# design.net
KiCad netlist of a schematic drawn in Altium Designer
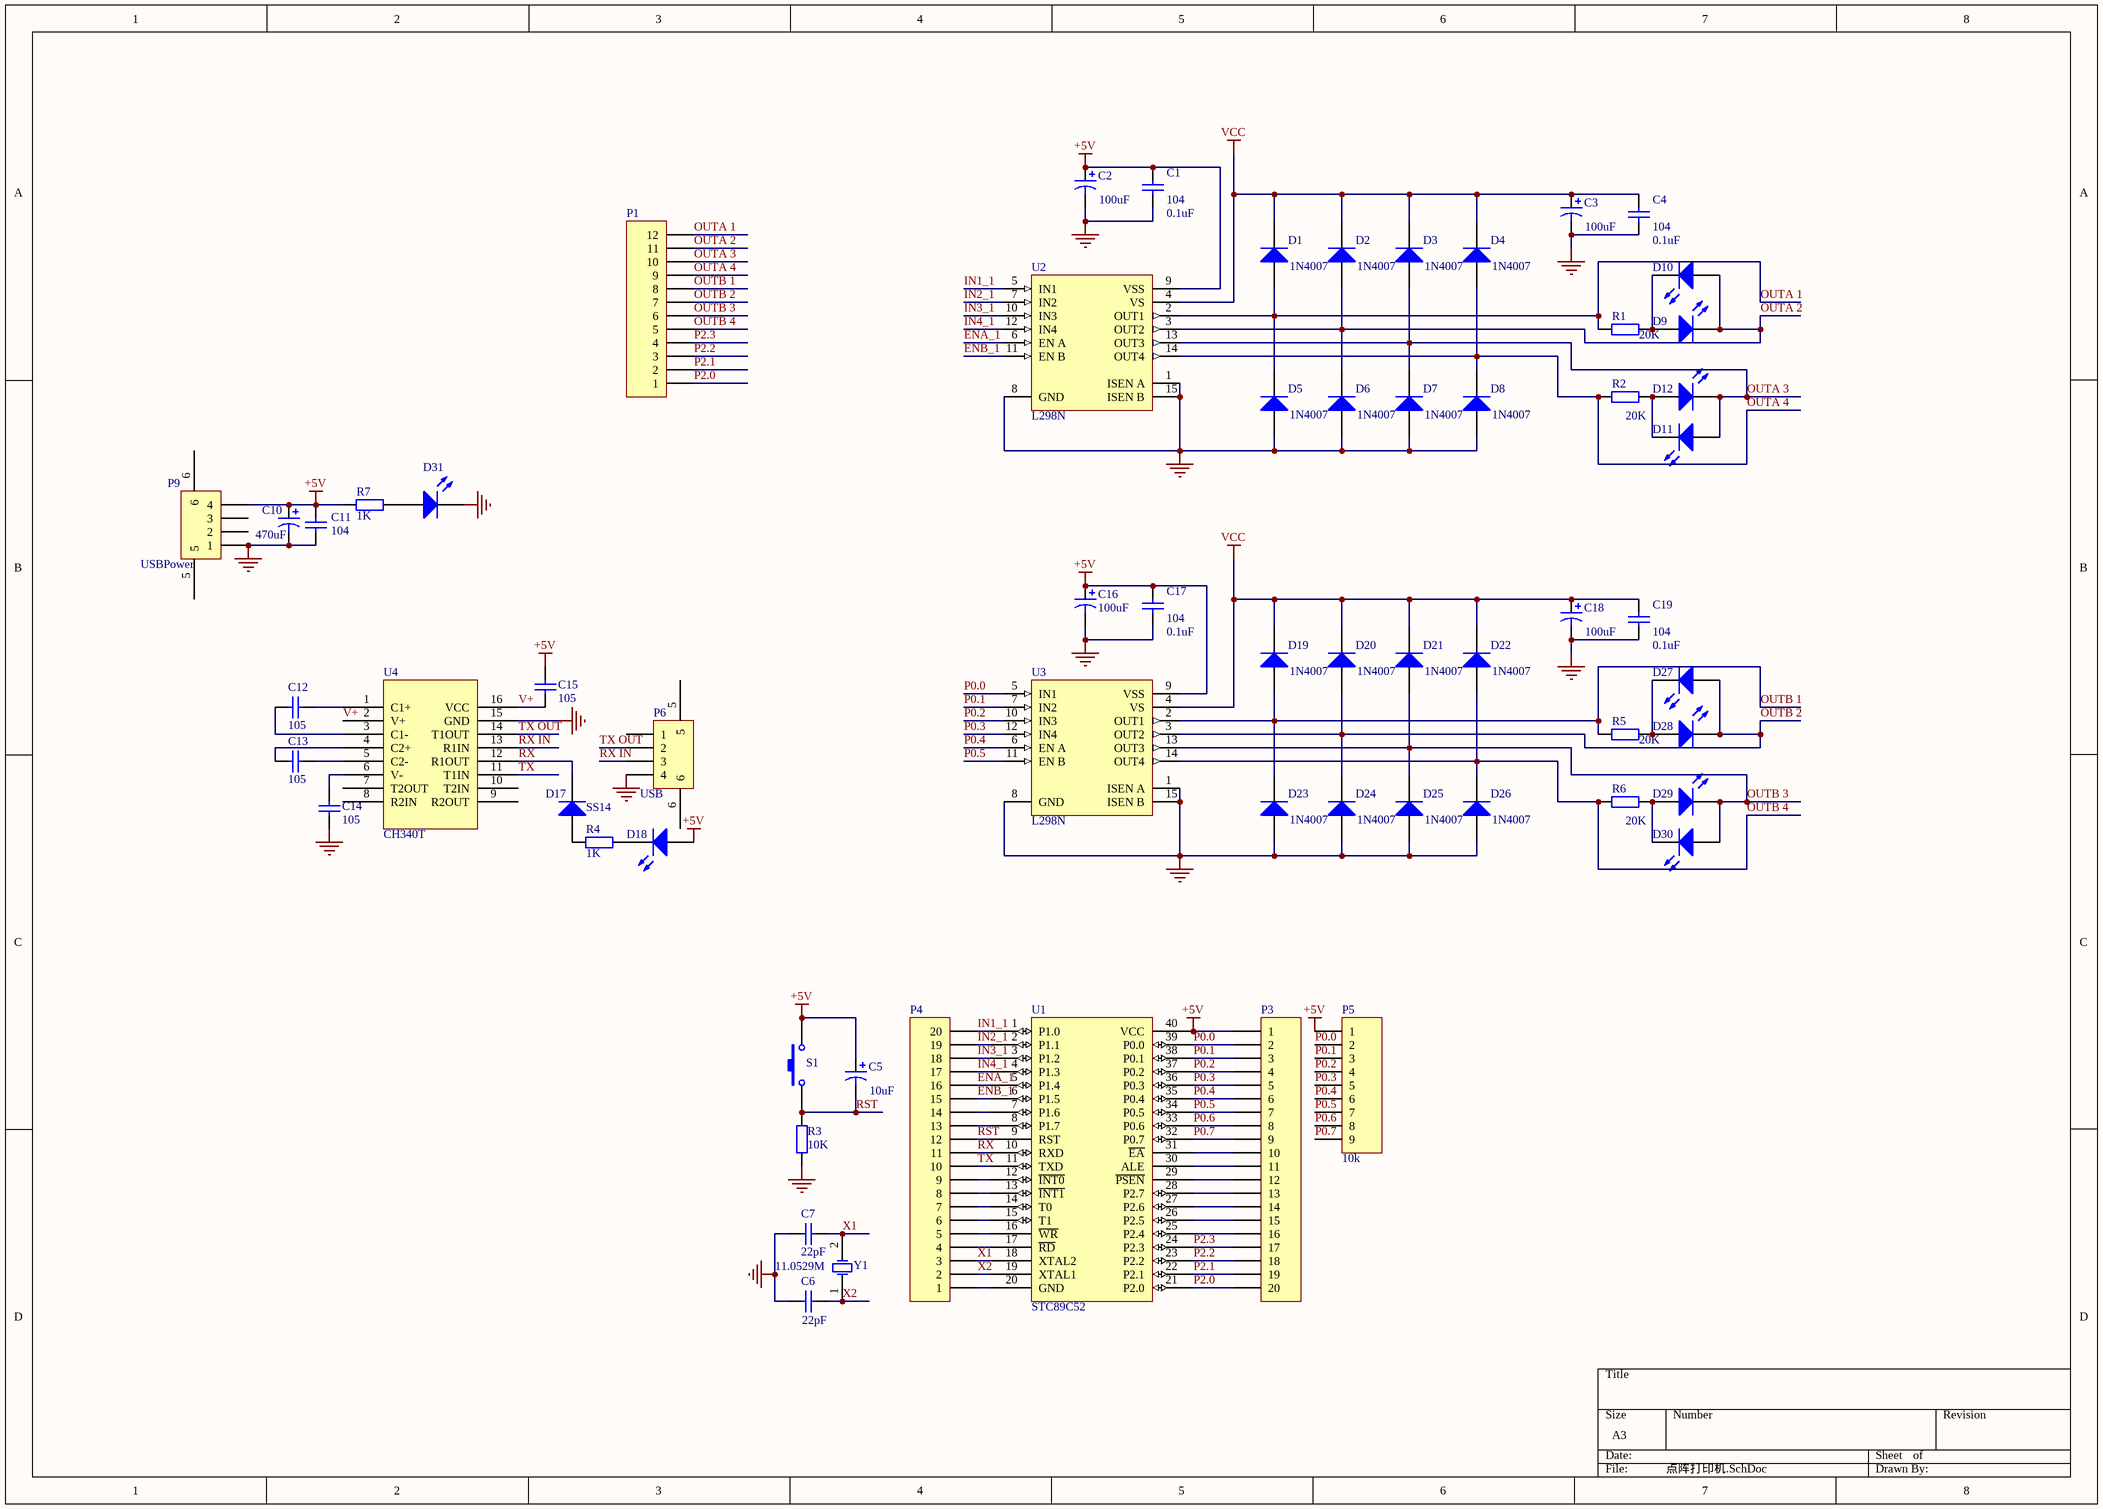
[diagram p0: 点阵打印机.SchDoc]

(export (version "E")
  (design (tool "Eeschema 10.0.6"))
  (components
    (comp (ref "C1")
      (value "0.1uF")
      (footprint "CB2")
      (description "Capacitor")
      (fields
        (field (name "ALTIUM_UNNAMED_1") "104")
        (field (name "Comment") "Cap")
        (field (name "PUBLISHER") "Altium Limited")
      )
      (libsource (lib "Miscellaneous Devices") (part "Cap"))
    )
    (comp (ref "C2")
      (value "100uF")
      (footprint "CD10")
      (description "Polarized Capacitor (Radial)")
      (fields (field (name "Comment") "Cap Pol1") (field (name "PUBLISHER") "Altium Limited"))
      (libsource (lib "Miscellaneous Devices") (part "Cap Pol1"))
    )
    (comp (ref "C3")
      (value "100uF")
      (footprint "CD10")
      (description "Polarized Capacitor (Radial)")
      (fields (field (name "Comment") "Cap Pol1") (field (name "PUBLISHER") "Altium Limited"))
      (libsource (lib "Miscellaneous Devices") (part "Cap Pol1"))
    )
    (comp (ref "C4")
      (value "0.1uF")
      (footprint "CB2")
      (description "Capacitor")
      (fields
        (field (name "ALTIUM_UNNAMED_1") "104")
        (field (name "Comment") "Cap")
        (field (name "PUBLISHER") "Altium Limited")
      )
      (libsource (lib "Miscellaneous Devices") (part "Cap"))
    )
    (comp (ref "C5")
      (value "10uF")
      (footprint "CD10")
      (description "Polarized Capacitor (Radial)")
      (fields (field (name "Comment") "Cap Pol1") (field (name "PUBLISHER") "Altium Limited"))
      (libsource (lib "Miscellaneous Devices") (part "Cap Pol1"))
    )
    (comp (ref "C6")
      (value "22pF")
      (footprint "CB2")
      (description "Capacitor")
      (fields (field (name "Comment") "Cap") (field (name "PUBLISHER") "Altium Limited"))
      (libsource (lib "Miscellaneous Devices") (part "Cap"))
    )
    (comp (ref "C7")
      (value "22pF")
      (footprint "CB2")
      (description "Capacitor")
      (fields (field (name "Comment") "Cap") (field (name "PUBLISHER") "Altium Limited"))
      (libsource (lib "Miscellaneous Devices") (part "Cap"))
    )
    (comp (ref "C10")
      (value "470uF")
      (footprint "CD10")
      (description "Polarized Capacitor (Radial)")
      (fields (field (name "Comment") "Cap Pol1") (field (name "PUBLISHER") "Altium Limited"))
      (libsource (lib "Miscellaneous Devices") (part "Cap Pol1"))
    )
    (comp (ref "C11")
      (value "104")
      (footprint "CB2")
      (description "Capacitor")
      (fields (field (name "Comment") "Cap") (field (name "PUBLISHER") "Altium Limited"))
      (libsource (lib "Miscellaneous Devices") (part "Cap"))
    )
    (comp (ref "C12")
      (value "105")
      (footprint "CB2")
      (description "Capacitor")
      (fields (field (name "Comment") "Cap") (field (name "PUBLISHER") "Altium Limited"))
      (libsource (lib "Miscellaneous Devices") (part "Cap"))
    )
    (comp (ref "C13")
      (value "105")
      (footprint "CB2")
      (description "Capacitor")
      (fields (field (name "Comment") "Cap") (field (name "PUBLISHER") "Altium Limited"))
      (libsource (lib "Miscellaneous Devices") (part "Cap"))
    )
    (comp (ref "C14")
      (value "105")
      (footprint "CB2")
      (description "Capacitor")
      (fields (field (name "Comment") "Cap") (field (name "PUBLISHER") "Altium Limited"))
      (libsource (lib "Miscellaneous Devices") (part "Cap"))
    )
    (comp (ref "C15")
      (value "105")
      (footprint "CB2")
      (description "Capacitor")
      (fields (field (name "Comment") "Cap") (field (name "PUBLISHER") "Altium Limited"))
      (libsource (lib "Miscellaneous Devices") (part "Cap"))
    )
    (comp (ref "C16")
      (value "100uF")
      (footprint "CD10")
      (description "Polarized Capacitor (Radial)")
      (fields (field (name "Comment") "Cap Pol1") (field (name "PUBLISHER") "Altium Limited"))
      (libsource (lib "Miscellaneous Devices") (part "Cap Pol1"))
    )
    (comp (ref "C17")
      (value "0.1uF")
      (footprint "CB2")
      (description "Capacitor")
      (fields
        (field (name "ALTIUM_UNNAMED_1") "104")
        (field (name "Comment") "Cap")
        (field (name "PUBLISHER") "Altium Limited")
      )
      (libsource (lib "Miscellaneous Devices") (part "Cap"))
    )
    (comp (ref "C18")
      (value "100uF")
      (footprint "CD10")
      (description "Polarized Capacitor (Radial)")
      (fields (field (name "Comment") "Cap Pol1") (field (name "PUBLISHER") "Altium Limited"))
      (libsource (lib "Miscellaneous Devices") (part "Cap Pol1"))
    )
    (comp (ref "C19")
      (value "0.1uF")
      (footprint "CB2")
      (description "Capacitor")
      (fields
        (field (name "ALTIUM_UNNAMED_1") "104")
        (field (name "Comment") "Cap")
        (field (name "PUBLISHER") "Altium Limited")
      )
      (libsource (lib "Miscellaneous Devices") (part "Cap"))
    )
    (comp (ref "D1")
      (value "1N4007")
      (footprint "DO-41")
      (description "1 Amp General Purpose Rectifier")
      (fields (field (name "PUBLISHER") "Altium Limited"))
      (libsource (lib "Miscellaneous Devices") (part "Diode 1N4007"))
    )
    (comp (ref "D2")
      (value "1N4007")
      (footprint "DO-41")
      (description "1 Amp General Purpose Rectifier")
      (fields (field (name "PUBLISHER") "Altium Limited"))
      (libsource (lib "Miscellaneous Devices") (part "Diode 1N4007"))
    )
    (comp (ref "D3")
      (value "1N4007")
      (footprint "DO-41")
      (description "1 Amp General Purpose Rectifier")
      (fields (field (name "PUBLISHER") "Altium Limited"))
      (libsource (lib "Miscellaneous Devices") (part "Diode 1N4007"))
    )
    (comp (ref "D4")
      (value "1N4007")
      (footprint "DO-41")
      (description "1 Amp General Purpose Rectifier")
      (fields (field (name "PUBLISHER") "Altium Limited"))
      (libsource (lib "Miscellaneous Devices") (part "Diode 1N4007"))
    )
    (comp (ref "D5")
      (value "1N4007")
      (footprint "DO-41")
      (description "1 Amp General Purpose Rectifier")
      (fields (field (name "PUBLISHER") "Altium Limited"))
      (libsource (lib "Miscellaneous Devices") (part "Diode 1N4007"))
    )
    (comp (ref "D6")
      (value "1N4007")
      (footprint "DO-41")
      (description "1 Amp General Purpose Rectifier")
      (fields (field (name "PUBLISHER") "Altium Limited"))
      (libsource (lib "Miscellaneous Devices") (part "Diode 1N4007"))
    )
    (comp (ref "D7")
      (value "1N4007")
      (footprint "DO-41")
      (description "1 Amp General Purpose Rectifier")
      (fields (field (name "PUBLISHER") "Altium Limited"))
      (libsource (lib "Miscellaneous Devices") (part "Diode 1N4007"))
    )
    (comp (ref "D8")
      (value "1N4007")
      (footprint "DO-41")
      (description "1 Amp General Purpose Rectifier")
      (fields (field (name "PUBLISHER") "Altium Limited"))
      (libsource (lib "Miscellaneous Devices") (part "Diode 1N4007"))
    )
    (comp (ref "D9")
      (value "LED0")
      (footprint "LED")
      (description "Typical INFRARED GaAs LED")
      (fields (field (name "PUBLISHER") "Altium Limited"))
      (libsource (lib "Miscellaneous Devices") (part "LED0"))
    )
    (comp (ref "D10")
      (value "LED0")
      (footprint "LED")
      (description "Typical INFRARED GaAs LED")
      (fields (field (name "PUBLISHER") "Altium Limited"))
      (libsource (lib "Miscellaneous Devices") (part "LED0"))
    )
    (comp (ref "D11")
      (value "LED0")
      (footprint "LED")
      (description "Typical INFRARED GaAs LED")
      (fields (field (name "PUBLISHER") "Altium Limited"))
      (libsource (lib "Miscellaneous Devices") (part "LED0"))
    )
    (comp (ref "D12")
      (value "LED0")
      (footprint "LED")
      (description "Typical INFRARED GaAs LED")
      (fields (field (name "PUBLISHER") "Altium Limited"))
      (libsource (lib "Miscellaneous Devices") (part "LED0"))
    )
    (comp (ref "D17")
      (value "SS14")
      (footprint "SMC")
      (description "Default Diode")
      (fields (field (name "PUBLISHER") "Altium Limited"))
      (libsource (lib "Miscellaneous Devices") (part "Diode"))
    )
    (comp (ref "D18")
      (value "LED0")
      (footprint "LED")
      (description "Typical INFRARED GaAs LED")
      (fields (field (name "PUBLISHER") "Altium Limited"))
      (libsource (lib "Miscellaneous Devices") (part "LED0"))
    )
    (comp (ref "D19")
      (value "1N4007")
      (footprint "DO-41")
      (description "1 Amp General Purpose Rectifier")
      (fields (field (name "PUBLISHER") "Altium Limited"))
      (libsource (lib "Miscellaneous Devices") (part "Diode 1N4007"))
    )
    (comp (ref "D20")
      (value "1N4007")
      (footprint "DO-41")
      (description "1 Amp General Purpose Rectifier")
      (fields (field (name "PUBLISHER") "Altium Limited"))
      (libsource (lib "Miscellaneous Devices") (part "Diode 1N4007"))
    )
    (comp (ref "D21")
      (value "1N4007")
      (footprint "DO-41")
      (description "1 Amp General Purpose Rectifier")
      (fields (field (name "PUBLISHER") "Altium Limited"))
      (libsource (lib "Miscellaneous Devices") (part "Diode 1N4007"))
    )
    (comp (ref "D22")
      (value "1N4007")
      (footprint "DO-41")
      (description "1 Amp General Purpose Rectifier")
      (fields (field (name "PUBLISHER") "Altium Limited"))
      (libsource (lib "Miscellaneous Devices") (part "Diode 1N4007"))
    )
    (comp (ref "D23")
      (value "1N4007")
      (footprint "DO-41")
      (description "1 Amp General Purpose Rectifier")
      (fields (field (name "PUBLISHER") "Altium Limited"))
      (libsource (lib "Miscellaneous Devices") (part "Diode 1N4007"))
    )
    (comp (ref "D24")
      (value "1N4007")
      (footprint "DO-41")
      (description "1 Amp General Purpose Rectifier")
      (fields (field (name "PUBLISHER") "Altium Limited"))
      (libsource (lib "Miscellaneous Devices") (part "Diode 1N4007"))
    )
    (comp (ref "D25")
      (value "1N4007")
      (footprint "DO-41")
      (description "1 Amp General Purpose Rectifier")
      (fields (field (name "PUBLISHER") "Altium Limited"))
      (libsource (lib "Miscellaneous Devices") (part "Diode 1N4007"))
    )
    (comp (ref "D26")
      (value "1N4007")
      (footprint "DO-41")
      (description "1 Amp General Purpose Rectifier")
      (fields (field (name "PUBLISHER") "Altium Limited"))
      (libsource (lib "Miscellaneous Devices") (part "Diode 1N4007"))
    )
    (comp (ref "D27")
      (value "LED0")
      (footprint "LED")
      (description "Typical INFRARED GaAs LED")
      (fields (field (name "PUBLISHER") "Altium Limited"))
      (libsource (lib "Miscellaneous Devices") (part "LED0"))
    )
    (comp (ref "D28")
      (value "LED0")
      (footprint "LED")
      (description "Typical INFRARED GaAs LED")
      (fields (field (name "PUBLISHER") "Altium Limited"))
      (libsource (lib "Miscellaneous Devices") (part "LED0"))
    )
    (comp (ref "D29")
      (value "LED0")
      (footprint "LED")
      (description "Typical INFRARED GaAs LED")
      (fields (field (name "PUBLISHER") "Altium Limited"))
      (libsource (lib "Miscellaneous Devices") (part "LED0"))
    )
    (comp (ref "D30")
      (value "LED0")
      (footprint "LED")
      (description "Typical INFRARED GaAs LED")
      (fields (field (name "PUBLISHER") "Altium Limited"))
      (libsource (lib "Miscellaneous Devices") (part "LED0"))
    )
    (comp (ref "D31")
      (value "LED0")
      (footprint "LED")
      (description "Typical INFRARED GaAs LED")
      (fields (field (name "PUBLISHER") "Altium Limited"))
      (libsource (lib "Miscellaneous Devices") (part "LED0"))
    )
    (comp (ref "P1")
      (value "Header 12")
      (footprint "HDR1X12")
      (description "Header, 12-Pin")
      (fields (field (name "PUBLISHER") "Altium Limited"))
      (libsource (lib "Miscellaneous Connectors") (part "Header 12"))
    )
    (comp (ref "P3")
      (value "Header 20")
      (footprint "HDR1X20")
      (description "Header, 20-Pin")
      (fields (field (name "PUBLISHER") "Altium Limited"))
      (libsource (lib "Miscellaneous Connectors") (part "Header 20"))
    )
    (comp (ref "P4")
      (value "Header 20")
      (footprint "HDR1X20")
      (description "Header, 20-Pin")
      (fields (field (name "PUBLISHER") "Altium Limited"))
      (libsource (lib "") (part "Header 20_1"))
    )
    (comp (ref "P5")
      (value "10k")
      (footprint "HDR1X9")
      (description "Header, 9-Pin")
      (fields (field (name "PUBLISHER") "Altium Limited"))
      (libsource (lib "Miscellaneous Connectors") (part "Header 9"))
    )
    (comp (ref "P6")
      (value "USB")
      (footprint "USB")
      (description "Header, 4-Pin")
      (fields (field (name "PUBLISHER") "Altium Limited"))
      (libsource (lib "") (part "Header 4_1"))
    )
    (comp (ref "P9")
      (value "USBPower")
      (footprint "USB")
      (description "Header, 4-Pin")
      (fields (field (name "PUBLISHER") "Altium Limited"))
      (libsource (lib "点阵打印机") (part "Header 4"))
    )
    (comp (ref "R1")
      (value "20K")
      (footprint "AXIAL-0.4")
      (description "Resistor")
      (fields (field (name "Comment") "Res2") (field (name "PUBLISHER") "Altium Limited"))
      (libsource (lib "Miscellaneous Devices") (part "Res2"))
    )
    (comp (ref "R2")
      (value "20K")
      (footprint "AXIAL-0.4")
      (description "Resistor")
      (fields (field (name "Comment") "Res2") (field (name "PUBLISHER") "Altium Limited"))
      (libsource (lib "Miscellaneous Devices") (part "Res2"))
    )
    (comp (ref "R3")
      (value "10K")
      (footprint "AXIAL-0.4")
      (description "Resistor")
      (fields (field (name "Comment") "Res2") (field (name "PUBLISHER") "Altium Limited"))
      (libsource (lib "") (part "Res2_1"))
    )
    (comp (ref "R4")
      (value "1K")
      (footprint "AXIAL-0.4")
      (description "Resistor")
      (fields (field (name "Comment") "Res2") (field (name "PUBLISHER") "Altium Limited"))
      (libsource (lib "Miscellaneous Devices") (part "Res2"))
    )
    (comp (ref "R5")
      (value "20K")
      (footprint "AXIAL-0.4")
      (description "Resistor")
      (fields (field (name "Comment") "Res2") (field (name "PUBLISHER") "Altium Limited"))
      (libsource (lib "Miscellaneous Devices") (part "Res2"))
    )
    (comp (ref "R6")
      (value "20K")
      (footprint "AXIAL-0.4")
      (description "Resistor")
      (fields (field (name "Comment") "Res2") (field (name "PUBLISHER") "Altium Limited"))
      (libsource (lib "Miscellaneous Devices") (part "Res2"))
    )
    (comp (ref "R7")
      (value "1K")
      (footprint "AXIAL-0.4")
      (description "Resistor")
      (fields (field (name "Comment") "Res2") (field (name "PUBLISHER") "Altium Limited"))
      (libsource (lib "") (part "Res2_2"))
    )
    (comp (ref "S1")
      (value "SW-PB")
      (footprint "KeyA")
      (description "Switch")
      (fields (field (name "PUBLISHER") "Altium Limited"))
      (libsource (lib "Miscellaneous Devices") (part "SW-PB"))
    )
    (comp (ref "U1") (value "STC89C52") (footprint "STC89C52") (libsource (lib "STC89C52") (part "STC89C52")))
    (comp (ref "U2")
      (value "L298N")
      (footprint "MULTIWATT15VA")
      (description "High-Current Switching Regulator")
      (fields (field (name "PUBLISHER") "Altium Limited"))
      (libsource (lib "点阵打印机") (part "L298N"))
    )
    (comp (ref "U3")
      (value "L298N")
      (footprint "MULTIWATT15VA")
      (description "High-Current Switching Regulator")
      (fields (field (name "PUBLISHER") "Altium Limited"))
      (libsource (lib "点阵打印机") (part "L298N"))
    )
    (comp (ref "U4") (value "CH340T") (footprint "MAX232CPE") (libsource (lib "点阵打印机") (part "MAX232CPE")))
    (comp (ref "Y1")
      (value "XTAL")
      (footprint "R38")
      (description "Crystal Oscillator")
      (fields (field (name "ALTIUM_UNNAMED_1") "11.0529M") (field (name "PUBLISHER") "Altium Limited"))
      (libsource (lib "Miscellaneous Devices") (part "XTAL"))
    )
  )
  (nets
    (net (code "1") (name "+5V") (class "Default")
      (node (ref "C1") (pin "2") (pinfunction "2_2") (pintype "passive"))
      (node (ref "C10") (pin "1") (pinfunction "1_1") (pintype "passive"))
      (node (ref "C11") (pin "2") (pinfunction "2_2") (pintype "passive"))
      (node (ref "C15") (pin "2") (pinfunction "2_2") (pintype "passive"))
      (node (ref "C16") (pin "1") (pinfunction "1_1") (pintype "passive"))
      (node (ref "C17") (pin "2") (pinfunction "2_2") (pintype "passive"))
      (node (ref "C2") (pin "1") (pinfunction "1_1") (pintype "passive"))
      (node (ref "C5") (pin "1") (pinfunction "1_1") (pintype "passive"))
      (node (ref "D18") (pin "1") (pinfunction "A_1") (pintype "passive"))
      (node (ref "P3") (pin "1") (pinfunction "1_1") (pintype "passive"))
      (node (ref "P5") (pin "1") (pinfunction "1_1") (pintype "passive"))
      (node (ref "P9") (pin "4") (pinfunction "4_4") (pintype "passive"))
      (node (ref "R7") (pin "2") (pinfunction "2_2") (pintype "passive"))
      (node (ref "S1") (pin "2") (pinfunction "2_2") (pintype "passive"))
      (node (ref "U1") (pin "40") (pinfunction "VCC_40") (pintype "power_in"))
      (node (ref "U2") (pin "9") (pinfunction "VSS_9") (pintype "power_in"))
      (node (ref "U3") (pin "9") (pinfunction "VSS_9") (pintype "power_in"))
    )
    (net (code "2") (name "/ENA_1") (class "Default")
      (node (ref "P4") (pin "16") (pinfunction "16_16") (pintype "passive"))
      (node (ref "U1") (pin "5") (pinfunction "P1.4_5") (pintype "bidirectional"))
      (node (ref "U2") (pin "6") (pinfunction "EN_A_6") (pintype "input"))
    )
    (net (code "3") (name "/ENB_1") (class "Default")
      (node (ref "P4") (pin "15") (pinfunction "15_15") (pintype "passive"))
      (node (ref "U1") (pin "6") (pinfunction "P1.5_6") (pintype "bidirectional"))
      (node (ref "U2") (pin "11") (pinfunction "EN_B_11") (pintype "input"))
    )
    (net (code "4") (name "/IN1_1") (class "Default")
      (node (ref "P4") (pin "20") (pinfunction "20_20") (pintype "passive"))
      (node (ref "U1") (pin "1") (pinfunction "P1.0_1") (pintype "bidirectional"))
      (node (ref "U2") (pin "5") (pinfunction "IN1_5") (pintype "input"))
    )
    (net (code "5") (name "/IN2_1") (class "Default")
      (node (ref "P4") (pin "19") (pinfunction "19_19") (pintype "passive"))
      (node (ref "U1") (pin "2") (pinfunction "P1.1_2") (pintype "bidirectional"))
      (node (ref "U2") (pin "7") (pinfunction "IN2_7") (pintype "input"))
    )
    (net (code "6") (name "/IN3_1") (class "Default")
      (node (ref "P4") (pin "18") (pinfunction "18_18") (pintype "passive"))
      (node (ref "U1") (pin "3") (pinfunction "P1.2_3") (pintype "bidirectional"))
      (node (ref "U2") (pin "10") (pinfunction "IN3_10") (pintype "input"))
    )
    (net (code "7") (name "/IN4_1") (class "Default")
      (node (ref "P4") (pin "17") (pinfunction "17_17") (pintype "passive"))
      (node (ref "U1") (pin "4") (pinfunction "P1.3_4") (pintype "bidirectional"))
      (node (ref "U2") (pin "12") (pinfunction "IN4_12") (pintype "input"))
    )
    (net (code "8") (name "/OUTA 1") (class "Default")
      (node (ref "D1") (pin "1") (pinfunction "A_1") (pintype "passive"))
      (node (ref "D5") (pin "2") (pinfunction "K_2") (pintype "passive"))
      (node (ref "P1") (pin "12") (pinfunction "12_12") (pintype "passive"))
      (node (ref "R1") (pin "1") (pinfunction "1_1") (pintype "passive"))
      (node (ref "U2") (pin "2") (pinfunction "OUT1_2") (pintype "output"))
    )
    (net (code "9") (name "/OUTA 2") (class "Default")
      (node (ref "D10") (pin "1") (pinfunction "A_1") (pintype "passive"))
      (node (ref "D2") (pin "1") (pinfunction "A_1") (pintype "passive"))
      (node (ref "D6") (pin "2") (pinfunction "K_2") (pintype "passive"))
      (node (ref "D9") (pin "2") (pinfunction "K_2") (pintype "passive"))
      (node (ref "P1") (pin "11") (pinfunction "11_11") (pintype "passive"))
      (node (ref "U2") (pin "3") (pinfunction "OUT2_3") (pintype "output"))
    )
    (net (code "10") (name "/OUTA 3") (class "Default")
      (node (ref "D11") (pin "1") (pinfunction "A_1") (pintype "passive"))
      (node (ref "D12") (pin "2") (pinfunction "K_2") (pintype "passive"))
      (node (ref "D3") (pin "1") (pinfunction "A_1") (pintype "passive"))
      (node (ref "D7") (pin "2") (pinfunction "K_2") (pintype "passive"))
      (node (ref "P1") (pin "10") (pinfunction "10_10") (pintype "passive"))
      (node (ref "U2") (pin "13") (pinfunction "OUT3_13") (pintype "output"))
    )
    (net (code "11") (name "/OUTA 4") (class "Default")
      (node (ref "D4") (pin "1") (pinfunction "A_1") (pintype "passive"))
      (node (ref "D8") (pin "2") (pinfunction "K_2") (pintype "passive"))
      (node (ref "P1") (pin "9") (pinfunction "9_9") (pintype "passive"))
      (node (ref "R2") (pin "1") (pinfunction "1_1") (pintype "passive"))
      (node (ref "U2") (pin "14") (pinfunction "OUT4_14") (pintype "output"))
    )
    (net (code "12") (name "/OUTB 1") (class "Default")
      (node (ref "D19") (pin "1") (pinfunction "A_1") (pintype "passive"))
      (node (ref "D23") (pin "2") (pinfunction "K_2") (pintype "passive"))
      (node (ref "P1") (pin "8") (pinfunction "8_8") (pintype "passive"))
      (node (ref "R5") (pin "1") (pinfunction "1_1") (pintype "passive"))
      (node (ref "U3") (pin "2") (pinfunction "OUT1_2") (pintype "output"))
    )
    (net (code "13") (name "/OUTB 2") (class "Default")
      (node (ref "D20") (pin "1") (pinfunction "A_1") (pintype "passive"))
      (node (ref "D24") (pin "2") (pinfunction "K_2") (pintype "passive"))
      (node (ref "D27") (pin "1") (pinfunction "A_1") (pintype "passive"))
      (node (ref "D28") (pin "2") (pinfunction "K_2") (pintype "passive"))
      (node (ref "P1") (pin "7") (pinfunction "7_7") (pintype "passive"))
      (node (ref "U3") (pin "3") (pinfunction "OUT2_3") (pintype "output"))
    )
    (net (code "14") (name "/OUTB 3") (class "Default")
      (node (ref "D21") (pin "1") (pinfunction "A_1") (pintype "passive"))
      (node (ref "D25") (pin "2") (pinfunction "K_2") (pintype "passive"))
      (node (ref "D29") (pin "2") (pinfunction "K_2") (pintype "passive"))
      (node (ref "D30") (pin "1") (pinfunction "A_1") (pintype "passive"))
      (node (ref "P1") (pin "6") (pinfunction "6_6") (pintype "passive"))
      (node (ref "U3") (pin "13") (pinfunction "OUT3_13") (pintype "output"))
    )
    (net (code "15") (name "/OUTB 4") (class "Default")
      (node (ref "D22") (pin "1") (pinfunction "A_1") (pintype "passive"))
      (node (ref "D26") (pin "2") (pinfunction "K_2") (pintype "passive"))
      (node (ref "P1") (pin "5") (pinfunction "5_5") (pintype "passive"))
      (node (ref "R6") (pin "1") (pinfunction "1_1") (pintype "passive"))
      (node (ref "U3") (pin "14") (pinfunction "OUT4_14") (pintype "output"))
    )
    (net (code "16") (name "/P0.0") (class "Default")
      (node (ref "P3") (pin "2") (pinfunction "2_2") (pintype "passive"))
      (node (ref "P5") (pin "2") (pinfunction "2_2") (pintype "passive"))
      (node (ref "U1") (pin "39") (pinfunction "P0.0_39") (pintype "bidirectional"))
      (node (ref "U3") (pin "5") (pinfunction "IN1_5") (pintype "input"))
    )
    (net (code "17") (name "/P0.1") (class "Default")
      (node (ref "P3") (pin "3") (pinfunction "3_3") (pintype "passive"))
      (node (ref "P5") (pin "3") (pinfunction "3_3") (pintype "passive"))
      (node (ref "U1") (pin "38") (pinfunction "P0.1_38") (pintype "bidirectional"))
      (node (ref "U3") (pin "7") (pinfunction "IN2_7") (pintype "input"))
    )
    (net (code "18") (name "/P0.2") (class "Default")
      (node (ref "P3") (pin "4") (pinfunction "4_4") (pintype "passive"))
      (node (ref "P5") (pin "4") (pinfunction "4_4") (pintype "passive"))
      (node (ref "U1") (pin "37") (pinfunction "P0.2_37") (pintype "bidirectional"))
      (node (ref "U3") (pin "10") (pinfunction "IN3_10") (pintype "input"))
    )
    (net (code "19") (name "/P0.3") (class "Default")
      (node (ref "P3") (pin "5") (pinfunction "5_5") (pintype "passive"))
      (node (ref "P5") (pin "5") (pinfunction "5_5") (pintype "passive"))
      (node (ref "U1") (pin "36") (pinfunction "P0.3_36") (pintype "bidirectional"))
      (node (ref "U3") (pin "12") (pinfunction "IN4_12") (pintype "input"))
    )
    (net (code "20") (name "/P0.4") (class "Default")
      (node (ref "P3") (pin "6") (pinfunction "6_6") (pintype "passive"))
      (node (ref "P5") (pin "6") (pinfunction "6_6") (pintype "passive"))
      (node (ref "U1") (pin "35") (pinfunction "P0.4_35") (pintype "bidirectional"))
      (node (ref "U3") (pin "6") (pinfunction "EN_A_6") (pintype "input"))
    )
    (net (code "21") (name "/P0.5") (class "Default")
      (node (ref "P3") (pin "7") (pinfunction "7_7") (pintype "passive"))
      (node (ref "P5") (pin "7") (pinfunction "7_7") (pintype "passive"))
      (node (ref "U1") (pin "34") (pinfunction "P0.5_34") (pintype "bidirectional"))
      (node (ref "U3") (pin "11") (pinfunction "EN_B_11") (pintype "input"))
    )
    (net (code "22") (name "/P0.6") (class "Default")
      (node (ref "P3") (pin "8") (pinfunction "8_8") (pintype "passive"))
      (node (ref "P5") (pin "8") (pinfunction "8_8") (pintype "passive"))
      (node (ref "U1") (pin "33") (pinfunction "P0.6_33") (pintype "bidirectional"))
    )
    (net (code "23") (name "/P0.7") (class "Default")
      (node (ref "P3") (pin "9") (pinfunction "9_9") (pintype "passive"))
      (node (ref "P5") (pin "9") (pinfunction "9_9") (pintype "passive"))
      (node (ref "U1") (pin "32") (pinfunction "P0.7_32") (pintype "bidirectional"))
    )
    (net (code "24") (name "/P2.0") (class "Default")
      (node (ref "P1") (pin "1") (pinfunction "1_1") (pintype "passive"))
      (node (ref "P3") (pin "20") (pinfunction "20_20") (pintype "passive"))
      (node (ref "U1") (pin "21") (pinfunction "P2.0_21") (pintype "bidirectional"))
    )
    (net (code "25") (name "/P2.1") (class "Default")
      (node (ref "P1") (pin "2") (pinfunction "2_2") (pintype "passive"))
      (node (ref "P3") (pin "19") (pinfunction "19_19") (pintype "passive"))
      (node (ref "U1") (pin "22") (pinfunction "P2.1_22") (pintype "bidirectional"))
    )
    (net (code "26") (name "/P2.2") (class "Default")
      (node (ref "P1") (pin "3") (pinfunction "3_3") (pintype "passive"))
      (node (ref "P3") (pin "18") (pinfunction "18_18") (pintype "passive"))
      (node (ref "U1") (pin "23") (pinfunction "P2.2_23") (pintype "bidirectional"))
    )
    (net (code "27") (name "/P2.3") (class "Default")
      (node (ref "P1") (pin "4") (pinfunction "4_4") (pintype "passive"))
      (node (ref "P3") (pin "17") (pinfunction "17_17") (pintype "passive"))
      (node (ref "U1") (pin "24") (pinfunction "P2.3_24") (pintype "bidirectional"))
    )
    (net (code "28") (name "/RST") (class "Default")
      (node (ref "C5") (pin "2") (pinfunction "2_2") (pintype "passive"))
      (node (ref "P4") (pin "12") (pinfunction "12_12") (pintype "passive"))
      (node (ref "R3") (pin "1") (pinfunction "1_1") (pintype "passive"))
      (node (ref "S1") (pin "1") (pinfunction "1_1") (pintype "passive"))
      (node (ref "U1") (pin "9") (pinfunction "RST_9") (pintype "passive"))
    )
    (net (code "29") (name "/RX") (class "Default")
      (node (ref "D17") (pin "2") (pinfunction "K_2") (pintype "passive"))
      (node (ref "P4") (pin "11") (pinfunction "11_11") (pintype "passive"))
      (node (ref "U1") (pin "10") (pinfunction "RXD_10") (pintype "bidirectional"))
      (node (ref "U4") (pin "12") (pinfunction "R1OUT_12") (pintype "passive"))
    )
    (net (code "30") (name "/RX IN") (class "Default")
      (node (ref "P6") (pin "3") (pinfunction "3_3") (pintype "passive"))
      (node (ref "U4") (pin "13") (pinfunction "R1IN_13") (pintype "passive"))
    )
    (net (code "31") (name "/TX") (class "Default")
      (node (ref "P4") (pin "10") (pinfunction "10_10") (pintype "passive"))
      (node (ref "U1") (pin "11") (pinfunction "TXD_11") (pintype "bidirectional"))
      (node (ref "U4") (pin "11") (pinfunction "T1IN_11") (pintype "passive"))
    )
    (net (code "32") (name "/TX OUT") (class "Default")
      (node (ref "P6") (pin "2") (pinfunction "2_2") (pintype "passive"))
      (node (ref "U4") (pin "14") (pinfunction "T1OUT_14") (pintype "passive"))
    )
    (net (code "33") (name "/V+") (class "Default")
      (node (ref "C15") (pin "1") (pinfunction "1_1") (pintype "passive"))
      (node (ref "U4") (pin "16") (pinfunction "VCC_16") (pintype "passive"))
      (node (ref "U4") (pin "2") (pinfunction "V+_2") (pintype "passive"))
    )
    (net (code "34") (name "/X1") (class "Default")
      (node (ref "C7") (pin "2") (pinfunction "2_2") (pintype "passive"))
      (node (ref "P4") (pin "3") (pinfunction "3_3") (pintype "passive"))
      (node (ref "U1") (pin "18") (pinfunction "XTAL2_18") (pintype "passive"))
      (node (ref "Y1") (pin "2") (pinfunction "OSC2_2") (pintype "passive"))
    )
    (net (code "35") (name "/X2") (class "Default")
      (node (ref "C6") (pin "2") (pinfunction "2_2") (pintype "passive"))
      (node (ref "P4") (pin "2") (pinfunction "2_2") (pintype "passive"))
      (node (ref "U1") (pin "19") (pinfunction "XTAL1_19") (pintype "passive"))
      (node (ref "Y1") (pin "1") (pinfunction "OSC1_1") (pintype "passive"))
    )
    (net (code "36") (name "GND") (class "Default")
      (node (ref "C1") (pin "1") (pinfunction "1_1") (pintype "passive"))
      (node (ref "C10") (pin "2") (pinfunction "2_2") (pintype "passive"))
      (node (ref "C11") (pin "1") (pinfunction "1_1") (pintype "passive"))
      (node (ref "C14") (pin "1") (pinfunction "1_1") (pintype "passive"))
      (node (ref "C16") (pin "2") (pinfunction "2_2") (pintype "passive"))
      (node (ref "C17") (pin "1") (pinfunction "1_1") (pintype "passive"))
      (node (ref "C18") (pin "2") (pinfunction "2_2") (pintype "passive"))
      (node (ref "C19") (pin "1") (pinfunction "1_1") (pintype "passive"))
      (node (ref "C2") (pin "2") (pinfunction "2_2") (pintype "passive"))
      (node (ref "C3") (pin "2") (pinfunction "2_2") (pintype "passive"))
      (node (ref "C4") (pin "1") (pinfunction "1_1") (pintype "passive"))
      (node (ref "C6") (pin "1") (pinfunction "1_1") (pintype "passive"))
      (node (ref "C7") (pin "1") (pinfunction "1_1") (pintype "passive"))
      (node (ref "D23") (pin "1") (pinfunction "A_1") (pintype "passive"))
      (node (ref "D24") (pin "1") (pinfunction "A_1") (pintype "passive"))
      (node (ref "D25") (pin "1") (pinfunction "A_1") (pintype "passive"))
      (node (ref "D26") (pin "1") (pinfunction "A_1") (pintype "passive"))
      (node (ref "D31") (pin "2") (pinfunction "K_2") (pintype "passive"))
      (node (ref "D5") (pin "1") (pinfunction "A_1") (pintype "passive"))
      (node (ref "D6") (pin "1") (pinfunction "A_1") (pintype "passive"))
      (node (ref "D7") (pin "1") (pinfunction "A_1") (pintype "passive"))
      (node (ref "D8") (pin "1") (pinfunction "A_1") (pintype "passive"))
      (node (ref "P6") (pin "4") (pinfunction "4_4") (pintype "passive"))
      (node (ref "P9") (pin "1") (pinfunction "1_1") (pintype "passive"))
      (node (ref "R3") (pin "2") (pinfunction "2_2") (pintype "passive"))
      (node (ref "U2") (pin "1") (pinfunction "ISEN_A_1") (pintype "passive"))
      (node (ref "U2") (pin "15") (pinfunction "ISEN_B_15") (pintype "passive"))
      (node (ref "U2") (pin "8") (pinfunction "GND_8") (pintype "power_in"))
      (node (ref "U3") (pin "1") (pinfunction "ISEN_A_1") (pintype "passive"))
      (node (ref "U3") (pin "15") (pinfunction "ISEN_B_15") (pintype "passive"))
      (node (ref "U3") (pin "8") (pinfunction "GND_8") (pintype "power_in"))
      (node (ref "U4") (pin "15") (pinfunction "GND_15") (pintype "passive"))
    )
    (net (code "37") (name "Net-(D10-K)") (class "Default")
      (node (ref "D10") (pin "2") (pinfunction "K_2") (pintype "passive"))
      (node (ref "D9") (pin "1") (pinfunction "A_1") (pintype "passive"))
      (node (ref "R1") (pin "2") (pinfunction "2_2") (pintype "passive"))
    )
    (net (code "38") (name "Net-(D11-K)") (class "Default")
      (node (ref "D11") (pin "2") (pinfunction "K_2") (pintype "passive"))
      (node (ref "D12") (pin "1") (pinfunction "A_1") (pintype "passive"))
      (node (ref "R2") (pin "2") (pinfunction "2_2") (pintype "passive"))
    )
    (net (code "39") (name "Net-(D17-A)") (class "Default")
      (node (ref "D17") (pin "1") (pinfunction "A_1") (pintype "passive"))
      (node (ref "R4") (pin "1") (pinfunction "1_1") (pintype "passive"))
    )
    (net (code "40") (name "Net-(D18-K)") (class "Default")
      (node (ref "D18") (pin "2") (pinfunction "K_2") (pintype "passive"))
      (node (ref "R4") (pin "2") (pinfunction "2_2") (pintype "passive"))
    )
    (net (code "41") (name "Net-(D27-K)") (class "Default")
      (node (ref "D27") (pin "2") (pinfunction "K_2") (pintype "passive"))
      (node (ref "D28") (pin "1") (pinfunction "A_1") (pintype "passive"))
      (node (ref "R5") (pin "2") (pinfunction "2_2") (pintype "passive"))
    )
    (net (code "42") (name "Net-(D29-A)") (class "Default")
      (node (ref "D29") (pin "1") (pinfunction "A_1") (pintype "passive"))
      (node (ref "D30") (pin "2") (pinfunction "K_2") (pintype "passive"))
      (node (ref "R6") (pin "2") (pinfunction "2_2") (pintype "passive"))
    )
    (net (code "43") (name "Net-(D31-A)") (class "Default")
      (node (ref "D31") (pin "1") (pinfunction "A_1") (pintype "passive"))
      (node (ref "R7") (pin "1") (pinfunction "1_1") (pintype "passive"))
    )
    (net (code "44") (name "Net-(U1-ALE)") (class "Default")
      (node (ref "P3") (pin "11") (pinfunction "11_11") (pintype "passive"))
      (node (ref "U1") (pin "30") (pinfunction "ALE_30") (pintype "passive"))
    )
    (net (code "45") (name "Net-(U1-GND)") (class "Default")
      (node (ref "P4") (pin "1") (pinfunction "1_1") (pintype "passive"))
      (node (ref "U1") (pin "20") (pinfunction "GND_20") (pintype "power_in"))
    )
    (net (code "46") (name "Net-(U1-P1.6)") (class "Default")
      (node (ref "P4") (pin "14") (pinfunction "14_14") (pintype "passive"))
      (node (ref "U1") (pin "7") (pinfunction "P1.6_7") (pintype "bidirectional"))
    )
    (net (code "47") (name "Net-(U1-P1.7)") (class "Default")
      (node (ref "P4") (pin "13") (pinfunction "13_13") (pintype "passive"))
      (node (ref "U1") (pin "8") (pinfunction "P1.7_8") (pintype "bidirectional"))
    )
    (net (code "48") (name "Net-(U1-P2.4)") (class "Default")
      (node (ref "P3") (pin "16") (pinfunction "16_16") (pintype "passive"))
      (node (ref "U1") (pin "25") (pinfunction "P2.4_25") (pintype "bidirectional"))
    )
    (net (code "49") (name "Net-(U1-P2.5)") (class "Default")
      (node (ref "P3") (pin "15") (pinfunction "15_15") (pintype "passive"))
      (node (ref "U1") (pin "26") (pinfunction "P2.5_26") (pintype "bidirectional"))
    )
    (net (code "50") (name "Net-(U1-P2.6)") (class "Default")
      (node (ref "P3") (pin "14") (pinfunction "14_14") (pintype "passive"))
      (node (ref "U1") (pin "27") (pinfunction "P2.6_27") (pintype "bidirectional"))
    )
    (net (code "51") (name "Net-(U1-P2.7)") (class "Default")
      (node (ref "P3") (pin "13") (pinfunction "13_13") (pintype "passive"))
      (node (ref "U1") (pin "28") (pinfunction "P2.7_28") (pintype "bidirectional"))
    )
    (net (code "52") (name "Net-(U1-T0)") (class "Default")
      (node (ref "P4") (pin "7") (pinfunction "7_7") (pintype "passive"))
      (node (ref "U1") (pin "14") (pinfunction "T0_14") (pintype "bidirectional"))
    )
    (net (code "53") (name "Net-(U1-T1)") (class "Default")
      (node (ref "P4") (pin "6") (pinfunction "6_6") (pintype "passive"))
      (node (ref "U1") (pin "15") (pinfunction "T1_15") (pintype "bidirectional"))
    )
    (net (code "54") (name "Net-(U1-~{EA})") (class "Default")
      (node (ref "P3") (pin "10") (pinfunction "10_10") (pintype "passive"))
      (node (ref "U1") (pin "31") (pinfunction "~{EA}_31") (pintype "passive"))
    )
    (net (code "55") (name "Net-(U1-~{INT0})") (class "Default")
      (node (ref "P4") (pin "9") (pinfunction "9_9") (pintype "passive"))
      (node (ref "U1") (pin "12") (pinfunction "~{INT0}_12") (pintype "bidirectional"))
    )
    (net (code "56") (name "Net-(U1-~{INT1})") (class "Default")
      (node (ref "P4") (pin "8") (pinfunction "8_8") (pintype "passive"))
      (node (ref "U1") (pin "13") (pinfunction "~{INT1}_13") (pintype "bidirectional"))
    )
    (net (code "57") (name "Net-(U1-~{PSEN})") (class "Default")
      (node (ref "P3") (pin "12") (pinfunction "12_12") (pintype "passive"))
      (node (ref "U1") (pin "29") (pinfunction "~{PSEN}_29") (pintype "passive"))
    )
    (net (code "58") (name "Net-(U1-~{RD})") (class "Default")
      (node (ref "P4") (pin "4") (pinfunction "4_4") (pintype "passive"))
      (node (ref "U1") (pin "17") (pinfunction "~{RD}_17") (pintype "passive"))
    )
    (net (code "59") (name "Net-(U1-~{WR})") (class "Default")
      (node (ref "P4") (pin "5") (pinfunction "5_5") (pintype "passive"))
      (node (ref "U1") (pin "16") (pinfunction "~{WR}_16") (pintype "passive"))
    )
    (net (code "60") (name "Net-(U4-C1+)") (class "Default")
      (node (ref "C12") (pin "2") (pinfunction "2_2") (pintype "passive"))
      (node (ref "U4") (pin "1") (pinfunction "C1+_1") (pintype "passive"))
    )
    (net (code "61") (name "Net-(U4-C1-)") (class "Default")
      (node (ref "C12") (pin "1") (pinfunction "1_1") (pintype "passive"))
      (node (ref "U4") (pin "3") (pinfunction "C1-_3") (pintype "passive"))
    )
    (net (code "62") (name "Net-(U4-C2+)") (class "Default")
      (node (ref "C13") (pin "1") (pinfunction "1_1") (pintype "passive"))
      (node (ref "U4") (pin "4") (pinfunction "C2+_4") (pintype "passive"))
    )
    (net (code "63") (name "Net-(U4-C2-)") (class "Default")
      (node (ref "C13") (pin "2") (pinfunction "2_2") (pintype "passive"))
      (node (ref "U4") (pin "5") (pinfunction "C2-_5") (pintype "passive"))
    )
    (net (code "64") (name "Net-(U4-V-)") (class "Default")
      (node (ref "C14") (pin "2") (pinfunction "2_2") (pintype "passive"))
      (node (ref "U4") (pin "6") (pinfunction "V-_6") (pintype "passive"))
    )
    (net (code "65") (name "VCC") (class "Default")
      (node (ref "C18") (pin "1") (pinfunction "1_1") (pintype "passive"))
      (node (ref "C19") (pin "2") (pinfunction "2_2") (pintype "passive"))
      (node (ref "C3") (pin "1") (pinfunction "1_1") (pintype "passive"))
      (node (ref "C4") (pin "2") (pinfunction "2_2") (pintype "passive"))
      (node (ref "D1") (pin "2") (pinfunction "K_2") (pintype "passive"))
      (node (ref "D19") (pin "2") (pinfunction "K_2") (pintype "passive"))
      (node (ref "D2") (pin "2") (pinfunction "K_2") (pintype "passive"))
      (node (ref "D20") (pin "2") (pinfunction "K_2") (pintype "passive"))
      (node (ref "D21") (pin "2") (pinfunction "K_2") (pintype "passive"))
      (node (ref "D22") (pin "2") (pinfunction "K_2") (pintype "passive"))
      (node (ref "D3") (pin "2") (pinfunction "K_2") (pintype "passive"))
      (node (ref "D4") (pin "2") (pinfunction "K_2") (pintype "passive"))
      (node (ref "U2") (pin "4") (pinfunction "VS_4") (pintype "power_in"))
      (node (ref "U3") (pin "4") (pinfunction "VS_4") (pintype "power_in"))
    )
    (net (code "66") (name "unconnected-(P6-Pad1)") (class "Default")
      (node (ref "P6") (pin "1") (pinfunction "1_1") (pintype "passive"))
    )
    (net (code "67") (name "unconnected-(P6-Pad5)") (class "Default")
      (node (ref "P6") (pin "5") (pinfunction "5_5") (pintype "passive"))
    )
    (net (code "68") (name "unconnected-(P6-Pad6)") (class "Default")
      (node (ref "P6") (pin "6") (pinfunction "6_6") (pintype "passive"))
    )
    (net (code "69") (name "unconnected-(P9-Pad2)") (class "Default")
      (node (ref "P9") (pin "2") (pinfunction "2_2") (pintype "passive"))
    )
    (net (code "70") (name "unconnected-(P9-Pad3)") (class "Default")
      (node (ref "P9") (pin "3") (pinfunction "3_3") (pintype "passive"))
    )
    (net (code "71") (name "unconnected-(P9-Pad5)") (class "Default")
      (node (ref "P9") (pin "5") (pinfunction "5_5") (pintype "passive"))
    )
    (net (code "72") (name "unconnected-(P9-Pad6)") (class "Default")
      (node (ref "P9") (pin "6") (pinfunction "6_6") (pintype "passive"))
    )
    (net (code "73") (name "unconnected-(U4-R2IN-Pad8)") (class "Default")
      (node (ref "U4") (pin "8") (pinfunction "R2IN_8") (pintype "passive"))
    )
    (net (code "74") (name "unconnected-(U4-R2OUT-Pad9)") (class "Default")
      (node (ref "U4") (pin "9") (pinfunction "R2OUT_9") (pintype "passive"))
    )
    (net (code "75") (name "unconnected-(U4-T2IN-Pad10)") (class "Default")
      (node (ref "U4") (pin "10") (pinfunction "T2IN_10") (pintype "passive"))
    )
    (net (code "76") (name "unconnected-(U4-T2OUT-Pad7)") (class "Default")
      (node (ref "U4") (pin "7") (pinfunction "T2OUT_7") (pintype "passive"))
    )
  )
)
